# Other.net
KiCad netlist of a schematic drawn in Altium Designer
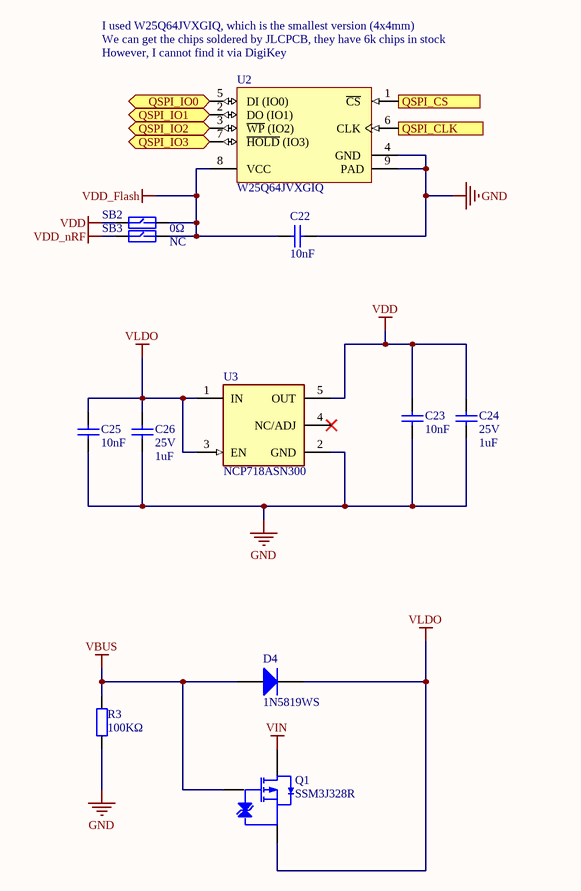
[diagram p0: Other.SchDoc]

(export (version "E")
  (design (tool "Eeschema 10.0.6"))
  (components
    (comp (ref "C22")
      (value "10nF")
      (footprint "0402_C")
      (description "Chip Capacitor")
      (fields (field (name "VOLTAGE") "50V") (field (name "Comment") "10nF (103) 10% 50V"))
      (libsource (lib "LocalLib") (part "0402 10nF (103) 10% 50V"))
    )
    (comp (ref "C23")
      (value "10nF")
      (footprint "0402_C")
      (description "Chip Capacitor")
      (fields (field (name "VOLTAGE") "50V") (field (name "Comment") "10nF (103) 10% 50V"))
      (libsource (lib "LocalLib") (part "0402 10nF (103) 10% 50V"))
    )
    (comp (ref "C24")
      (value "1uF")
      (footprint "0402_C")
      (description "Chip Capacitor")
      (fields (field (name "VOLTAGE") "25V") (field (name "Comment") "1uF (105) 10% 25V"))
      (libsource (lib "LocalLib") (part "0402 1uF (105) 10% 25V"))
    )
    (comp (ref "C25")
      (value "10nF")
      (footprint "0402_C")
      (description "Chip Capacitor")
      (fields (field (name "VOLTAGE") "50V") (field (name "Comment") "10nF (103) 10% 50V"))
      (libsource (lib "LocalLib") (part "0402 10nF (103) 10% 50V"))
    )
    (comp (ref "C26")
      (value "1uF")
      (footprint "0402_C")
      (description "Chip Capacitor")
      (fields (field (name "VOLTAGE") "25V") (field (name "Comment") "1uF (105) 10% 25V"))
      (libsource (lib "LocalLib") (part "0402 1uF (105) 10% 25V"))
    )
    (comp (ref "D4")
      (value "1N5819WS")
      (footprint "SOD-323")
      (fields (field (name "JLCPCB PART NUMBER") "C191023"))
      (libsource (lib "LocalLib") (part "1N5819WS"))
    )
    (comp (ref "Q1")
      (value "SSM3J328R")
      (footprint "SOT-23-3L")
      (description "20V 6A 29.8mΩ@4.5V,3A 1W P Channel SOT-23(TO-236)  MOSFETs ROHS")
      (libsource (lib "LocalLib") (part "SSM3J328R"))
    )
    (comp (ref "R3")
      (value "100KΩ")
      (footprint "0402_R")
      (description "Chip Resistor")
      (fields (field (name "Comment") "100KΩ (1003) ±1%"))
      (libsource (lib "LocalLib") (part "0402 100KΩ (1003) 1%"))
    )
    (comp (ref "SB2")
      (value "0Ω")
      (footprint "0603-FUSE")
      (description "Fuse easy soldering for test")
      (libsource (lib "LocalLib") (part "Test-Fuse"))
    )
    (comp (ref "SB3")
      (value "NC")
      (footprint "0603-FUSE")
      (description "Fuse easy soldering for test")
      (libsource (lib "LocalLib") (part "Test-Fuse"))
    )
    (comp (ref "U2")
      (value "W25Q64JVXGIQ")
      (footprint "W25Qxx-xSON127P600-8N")
      (fields
        (field (name "MANUFACTURER") "Winbond")
        (field (name "MANUFACTURER PART NUMBER") "W25Q64FVSSIG")
      )
      (libsource (lib "LocalLib") (part "W25Q64JVXGIQ"))
    )
    (comp (ref "U3")
      (value "NCP718ASN300")
      (footprint "SOT-23-5L")
      (description "3V LDO 300 MA LOW IQ WIDE INPUT")
      (fields
        (field (name "OCTOPART") "https://octopart.com/ncp718bsnadjt1g-on+semiconductor-87658781")
        (field (name "MANUFACTURER PART NUMBER") "NCP718BSNADJT1G")
      )
      (libsource (lib "LocalLib") (part "NCP718ASN300"))
    )
  )
  (nets
    (net (code "1") (name "/QSPI_CLK") (class "Default")
      (node (ref "U2") (pin "6") (pinfunction "CLK_6") (pintype "input"))
    )
    (net (code "2") (name "/QSPI_CS") (class "Default")
      (node (ref "U2") (pin "1") (pinfunction "~{CS}_1") (pintype "input"))
    )
    (net (code "3") (name "/QSPI_IO0") (class "Default")
      (node (ref "U2") (pin "5") (pinfunction "DI_(IO0)_5") (pintype "bidirectional"))
    )
    (net (code "4") (name "/QSPI_IO1") (class "Default")
      (node (ref "U2") (pin "2") (pinfunction "DO_(IO1)_2") (pintype "bidirectional"))
    )
    (net (code "5") (name "/QSPI_IO2") (class "Default")
      (node (ref "U2") (pin "3") (pinfunction "~{WP}_(IO2)_3") (pintype "bidirectional"))
    )
    (net (code "6") (name "/QSPI_IO3") (class "Default")
      (node (ref "U2") (pin "7") (pinfunction "~{HOLD}_(IO3)_7") (pintype "bidirectional"))
    )
    (net (code "7") (name "GND") (class "Default")
      (node (ref "C22") (pin "2") (pinfunction "2_2") (pintype "passive"))
      (node (ref "C23") (pin "1") (pinfunction "1_1") (pintype "passive"))
      (node (ref "C24") (pin "1") (pinfunction "1_1") (pintype "passive"))
      (node (ref "C25") (pin "1") (pinfunction "1_1") (pintype "passive"))
      (node (ref "C26") (pin "1") (pinfunction "1_1") (pintype "passive"))
      (node (ref "R3") (pin "1") (pinfunction "1_1") (pintype "passive"))
      (node (ref "U2") (pin "4") (pinfunction "GND_4") (pintype "power_in"))
      (node (ref "U2") (pin "9") (pinfunction "PAD_9") (pintype "passive"))
      (node (ref "U3") (pin "2") (pinfunction "GND_2") (pintype "power_in"))
    )
    (net (code "8") (name "VBUS") (class "Default")
      (node (ref "D4") (pin "1") (pinfunction "A_1") (pintype "passive"))
      (node (ref "Q1") (pin "1") (pinfunction "G_1") (pintype "passive"))
      (node (ref "R3") (pin "2") (pinfunction "2_2") (pintype "passive"))
    )
    (net (code "9") (name "VDD") (class "Default")
      (node (ref "C23") (pin "2") (pinfunction "2_2") (pintype "passive"))
      (node (ref "C24") (pin "2") (pinfunction "2_2") (pintype "passive"))
      (node (ref "SB2") (pin "1") (pinfunction "1_1") (pintype "passive"))
      (node (ref "U3") (pin "5") (pinfunction "OUT_5") (pintype "power_in"))
    )
    (net (code "10") (name "VDD_Flash") (class "Default")
      (node (ref "C22") (pin "1") (pinfunction "1_1") (pintype "passive"))
      (node (ref "SB2") (pin "2") (pinfunction "2_2") (pintype "passive"))
      (node (ref "SB3") (pin "2") (pinfunction "2_2") (pintype "passive"))
      (node (ref "U2") (pin "8") (pinfunction "VCC_8") (pintype "power_in"))
    )
    (net (code "11") (name "VDD_nRF") (class "Default")
      (node (ref "SB3") (pin "1") (pinfunction "1_1") (pintype "passive"))
    )
    (net (code "12") (name "VIN") (class "Default")
      (node (ref "Q1") (pin "3") (pinfunction "D_3") (pintype "passive"))
    )
    (net (code "13") (name "VLDO") (class "Default")
      (node (ref "C25") (pin "2") (pinfunction "2_2") (pintype "passive"))
      (node (ref "C26") (pin "2") (pinfunction "2_2") (pintype "passive"))
      (node (ref "D4") (pin "2") (pinfunction "K_2") (pintype "passive"))
      (node (ref "Q1") (pin "2") (pinfunction "S_2") (pintype "passive"))
      (node (ref "U3") (pin "1") (pinfunction "IN_1") (pintype "power_in"))
      (node (ref "U3") (pin "3") (pinfunction "EN_3") (pintype "input"))
    )
    (net (code "14") (name "unconnected-(U3-NC{slash}ADJ-Pad4)") (class "Default")
      (node (ref "U3") (pin "4") (pinfunction "NC/ADJ_4") (pintype "passive+no_connect"))
    )
  )
)
